# main_board.net
KiCad netlist of a schematic drawn in Altium Designer
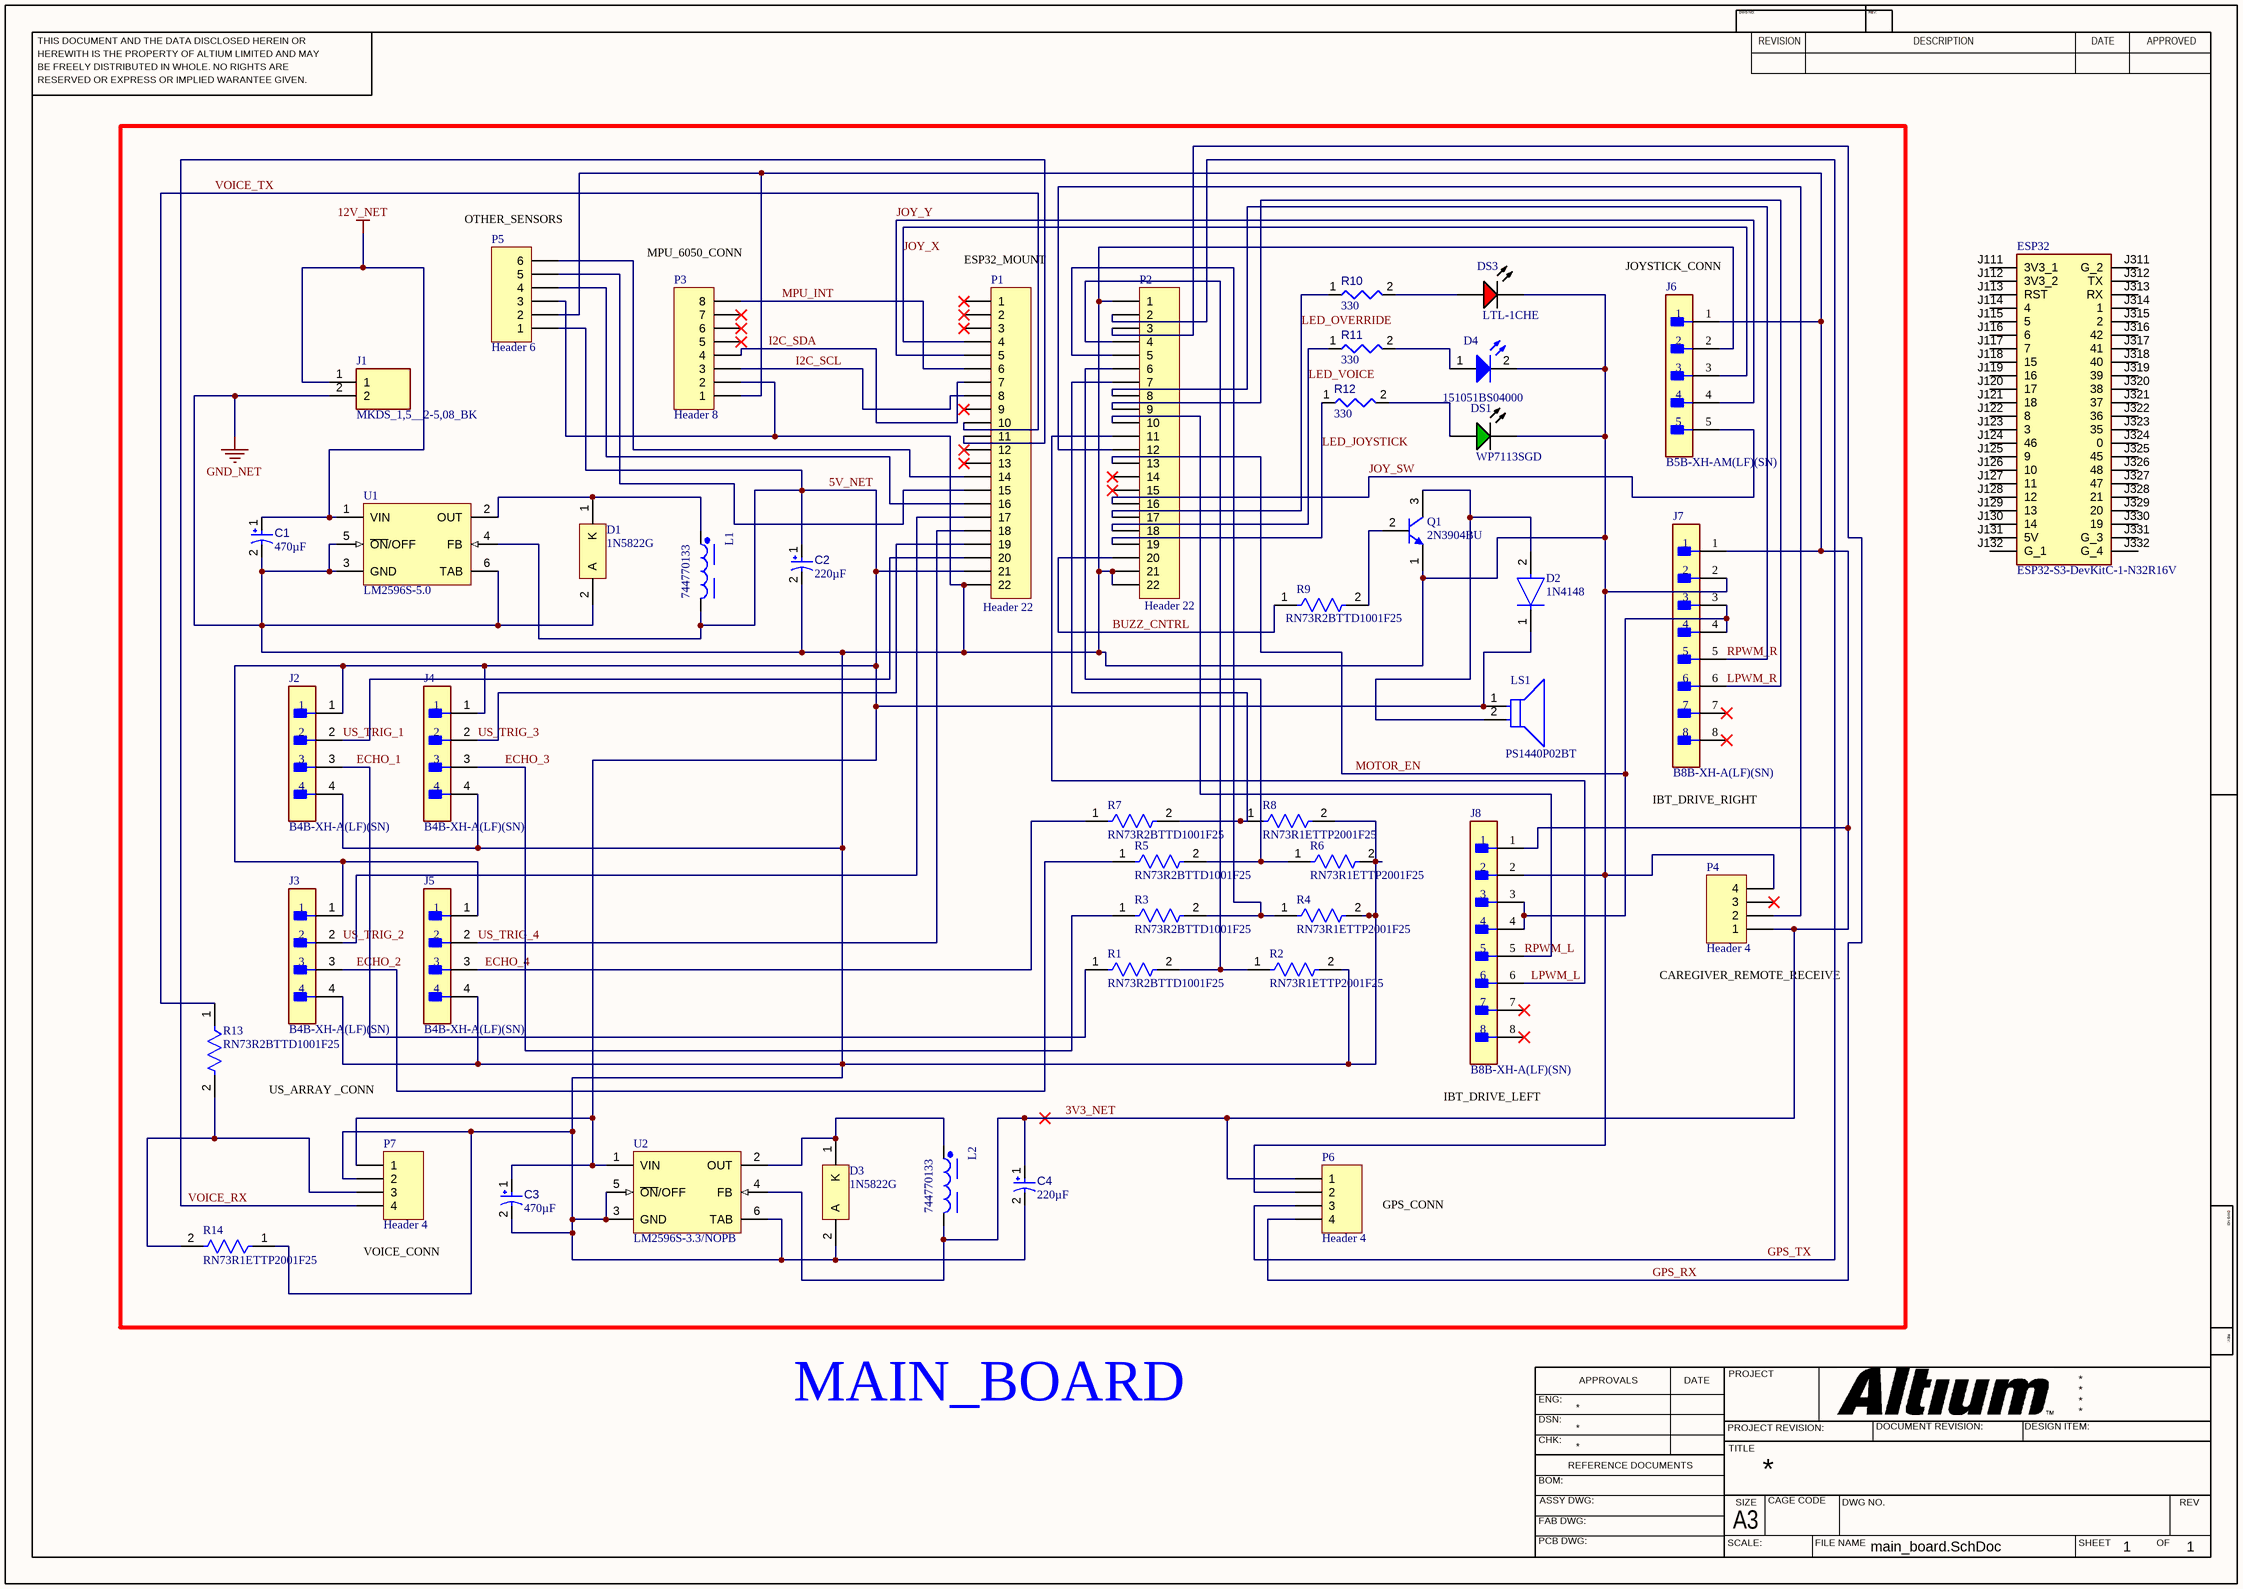
[diagram p0: main_board.SchDoc]

(export (version "E")
  (design (tool "Eeschema 10.0.6"))
  (components
    (comp (ref "C1")
      (value "470µF")
      (footprint "CAPPR65-500-2000X1000X2200")
      (description "Aluminum Electrolytic Capacitor, 470 uF, +/- 20%, 50 V, -40 to 85 degC, 2-Pin THD, RoHS, Bulk")
      (fields (field (name "TOLERANCE") "20%") (field (name "MANUFACTURER") "Panasonic"))
      (libsource (lib "RSM Priyanath") (part "CAP-P-2"))
    )
    (comp (ref "C2")
      (value "220µF")
      (footprint "CAPPR65-500-2000X1000X2200")
      (description "Aluminum Electrolytic Capacitor, 470 uF, +/- 20%, 50 V, -40 to 85 degC, 2-Pin THD, RoHS, Bulk")
      (fields (field (name "TOLERANCE") "20%") (field (name "MANUFACTURER") "Panasonic"))
      (libsource (lib "RSM Priyanath") (part "CAP-P-2"))
    )
    (comp (ref "C3")
      (value "470µF")
      (footprint "CAPPR65-500-2000X1000X2200")
      (description "Aluminum Electrolytic Capacitor, 470 uF, +/- 20%, 50 V, -40 to 85 degC, 2-Pin THD, RoHS, Bulk")
      (fields (field (name "TOLERANCE") "20%") (field (name "MANUFACTURER") "Panasonic"))
      (libsource (lib "RSM Priyanath") (part "CAP-P-2"))
    )
    (comp (ref "C4")
      (value "220µF")
      (footprint "CAPPR65-500-2000X1000X2200")
      (description "Aluminum Electrolytic Capacitor, 470 uF, +/- 20%, 50 V, -40 to 85 degC, 2-Pin THD, RoHS, Bulk")
      (fields (field (name "TOLERANCE") "20%") (field (name "MANUFACTURER") "Panasonic"))
      (libsource (lib "RSM Priyanath") (part "CAP-P-2"))
    )
    (comp (ref "D1")
      (value "1N5822G")
      (footprint "ONSC-AXIAL_LEAD-2-267-05_V")
      (description "Rectifier, 2-Pin Axial_Lead, Pb-Free, Bulk Bag")
      (fields (field (name "MANUFACTURER") "On Semiconductor"))
      (libsource (lib "Altium Content Vault") (part "ONSC-D-K1A2-2_A"))
    )
    (comp (ref "D2")
      (value "1N4148")
      (footprint "FP-017AG-MFG")
      (description "DIODE GEN PURP 100V 200MA DO35")
      (fields (field (name "VOLTAGE") "100V"))
      (libsource (lib "Altium Content Vault") (part "d7152d700b627762746794eb795d46e"))
    )
    (comp (ref "D3")
      (value "1N5822G")
      (footprint "ONSC-AXIAL_LEAD-2-267-05_V")
      (description "Rectifier, 2-Pin Axial_Lead, Pb-Free, Bulk Bag")
      (fields (field (name "MANUFACTURER") "On Semiconductor"))
      (libsource (lib "Altium Content Vault") (part "ONSC-D-K1A2-2_A"))
    )
    (comp (ref "D4")
      (value "151051BS04000")
      (footprint "WL-TMRC_D5.9H8.7")
      (description "Single Color LED, Blue, Diffused, T-1 3/4, 4.9mm")
      (libsource (lib "Altium Content Vault") (part "LED_Blue_1A-2K"))
    )
    (comp (ref "DS1")
      (value "WP7113SGD")
      (footprint "KING-WP7113SGD_V")
      (description "LED Green, 62.5 mW, 25 mA, -40 to 85 degC, 2-Pin THD, RoHS, Bulk")
      (fields (field (name "MANUFACTURER") "Kingbright") (field (name "POWER") "62.5mW"))
      (libsource (lib "RSM Priyanath") (part "LED-GREEN-AK-2"))
    )
    (comp (ref "DS3")
      (value "LTL-1CHE")
      (footprint "INDPR60-254-520X380X650")
      (description "LED Uni-Color Red, 100 mW, 30 mA, -55 to 100 degC, 2-Pin THD, RoHS, Bulk")
      (fields (field (name "MANUFACTURER") "Lite-On"))
      (libsource (lib "RSM Priyanath") (part "LED-RED-AK-2"))
    )
    (comp (ref "ESP32")
      (value "ESP32-S3-DevKitC-1-N32R16V")
      (footprint "SamacSys:ESP32S3DevKitC1N32R16V")
      (description "Undefined or Miscellaneous")
      (fields (field (name "MOUSER PART NUMBER") "356-32S3DKTC1N32R16V"))
      (libsource (lib "*") (part "ESP32-S3-DevKitC-1-N32R16V"))
    )
    (comp (ref "J1")
      (value "MKDS_1,5__2-5,08_BK")
      (footprint "SamacSys:MKDS152508BK")
      (description "Connector")
      (fields (field (name "MANUFACTURER_PART_NUMBER") "MKDS 1,5/ 2-5,08 BK"))
      (libsource (lib "*") (part "MKDS_1,5__2-5,08_BK"))
    )
    (comp (ref "J2")
      (value "B4B-XH-A(LF)(SN)")
      (footprint "FP-B4B-XH-A_LF_SN-MFG")
      (description "CONN HEADER VERT 4POS 2.5MM")
      (libsource (lib "Altium Content Vault") (part "299a8cea1bdcbc3624fe62c390fa72c"))
    )
    (comp (ref "J3")
      (value "B4B-XH-A(LF)(SN)")
      (footprint "FP-B4B-XH-A_LF_SN-MFG")
      (description "CONN HEADER VERT 4POS 2.5MM")
      (libsource (lib "Altium Content Vault") (part "299a8cea1bdcbc3624fe62c390fa72c"))
    )
    (comp (ref "J4")
      (value "B4B-XH-A(LF)(SN)")
      (footprint "FP-B4B-XH-A_LF_SN-MFG")
      (description "CONN HEADER VERT 4POS 2.5MM")
      (libsource (lib "Altium Content Vault") (part "299a8cea1bdcbc3624fe62c390fa72c"))
    )
    (comp (ref "J5")
      (value "B4B-XH-A(LF)(SN)")
      (footprint "FP-B4B-XH-A_LF_SN-MFG")
      (description "CONN HEADER VERT 4POS 2.5MM")
      (libsource (lib "Altium Content Vault") (part "299a8cea1bdcbc3624fe62c390fa72c"))
    )
    (comp (ref "J6")
      (value "B5B-XH-AM(LF)(SN)")
      (footprint "FP-B5B-XH-AM_LF_SN-MFG")
      (description "CONN HEADER VERT 5POS 2.5MM")
      (libsource (lib "Altium Content Vault") (part "bf93c07fd2649a848d0ec8585582aab"))
    )
    (comp (ref "J7")
      (value "B8B-XH-A(LF)(SN)")
      (footprint "FP-B8B-XH-A_LF_SN-MFG")
      (description "CONN HEADER VERT 8POS 2.5MM")
      (libsource (lib "Altium Content Vault") (part "99ec2b232beb5d2356d4d77f6a047f0"))
    )
    (comp (ref "J8")
      (value "B8B-XH-A(LF)(SN)")
      (footprint "FP-B8B-XH-A_LF_SN-MFG")
      (description "CONN HEADER VERT 8POS 2.5MM")
      (libsource (lib "Altium Content Vault") (part "99ec2b232beb5d2356d4d77f6a047f0"))
    )
    (comp (ref "L1")
      (value "744770133")
      (footprint "WE-PD_1280")
      (description "Power Choke Shielded Wirewound 33uH 20% 1KHz Ferrite 3.2A 64mOhm DCR T/R")
      (fields (field (name "TOLERANCE") "20%"))
      (libsource (lib "Altium Content Vault") (part "Inductor - 2"))
    )
    (comp (ref "L2")
      (value "744770133")
      (footprint "WE-PD_1280")
      (description "Power Choke Shielded Wirewound 33uH 20% 1KHz Ferrite 3.2A 64mOhm DCR T/R")
      (fields (field (name "TOLERANCE") "20%"))
      (libsource (lib "Altium Content Vault") (part "Inductor - 2"))
    )
    (comp (ref "LS1")
      (value "PS1440P02BT")
      (footprint "FP-PS1440P02BT-MFG")
      (description "AUDIO PIEZO TRANSDUCER 30V TH")
      (libsource (lib "Altium Content Vault") (part "5f581d31613f872430949aa526fd155"))
    )
    (comp (ref "P1")
      (value "Header 22")
      (footprint "HDR1X22")
      (description "Header, 22-Pin")
      (fields (field (name "PUBLISHER") "Altium Limited"))
      (libsource (lib "RSM Priyanath") (part "Header 22H"))
    )
    (comp (ref "P2")
      (value "Header 22")
      (footprint "HDR1X22")
      (description "Header, 22-Pin")
      (fields (field (name "PUBLISHER") "Altium Limited"))
      (libsource (lib "RSM Priyanath") (part "Header 22H"))
    )
    (comp (ref "P3")
      (value "Header 8")
      (footprint "HDR1X8")
      (description "Header, 8-Pin")
      (fields (field (name "PUBLISHER") "Altium Limited"))
      (libsource (lib "RSM Priyanath") (part "Header 8H"))
    )
    (comp (ref "P4")
      (value "Header 4")
      (footprint "HDR1X4")
      (description "Header, 4-Pin")
      (fields (field (name "PUBLISHER") "Altium Limited"))
      (libsource (lib "") (part "Header 4H_1"))
    )
    (comp (ref "P5")
      (value "Header 6")
      (footprint "HDR1X6")
      (description "Header, 6-Pin")
      (fields (field (name "PUBLISHER") "Altium Limited"))
      (libsource (lib "RSM Priyanath") (part "Header 6H"))
    )
    (comp (ref "P6")
      (value "Header 4")
      (footprint "HDR1X4")
      (description "Header, 4-Pin")
      (fields (field (name "PUBLISHER") "Altium Limited"))
      (libsource (lib "RSM Priyanath") (part "Header 4H"))
    )
    (comp (ref "P7")
      (value "Header 4")
      (footprint "HDR1X4")
      (description "Header, 4-Pin")
      (fields (field (name "PUBLISHER") "Altium Limited"))
      (libsource (lib "RSM Priyanath") (part "Header 4H"))
    )
    (comp (ref "Q1")
      (value "2N3904BU")
      (footprint "FAIR-TO-92")
      (description "NPN General-Purpose Amplifier, 40 V VCEO, 0.2 A, -55 to 150 degC, 2-Pin TO-92, RoHS, Bulk")
      (fields (field (name "MANUFACTURER") "FairchildSemiconductor"))
      (libsource (lib "Altium Content Vault") (part "NPN-E1B2C3-3"))
    )
    (comp (ref "R1")
      (value "RN73R2BTTD1001F25")
      (footprint "FP-RN73R2B-MFG")
      (description "1kΩ ±1% 0.25W, 1/4W Chip Resistor 1206 (3216 Metric) Moisture Resistant Thin Film")
      (libsource (lib "Altium Content Vault") (part "1029c3af85768c4190bb7ad29bc67b5"))
    )
    (comp (ref "R2")
      (value "RN73R1ETTP2001F25")
      (footprint "FP-RN73R1E-IPC_B")
      (description "2kΩ ±1% 0.063W, 1/16W Chip Resistor 0402 (1005 Metric) Moisture Resistant Thin Film")
      (libsource (lib "Altium Content Vault") (part "1029c3af85768c4190bb7ad29bc67b5"))
    )
    (comp (ref "R3")
      (value "RN73R2BTTD1001F25")
      (footprint "FP-RN73R2B-MFG")
      (description "1kΩ ±1% 0.25W, 1/4W Chip Resistor 1206 (3216 Metric) Moisture Resistant Thin Film")
      (libsource (lib "Altium Content Vault") (part "1029c3af85768c4190bb7ad29bc67b5"))
    )
    (comp (ref "R4")
      (value "RN73R1ETTP2001F25")
      (footprint "FP-RN73R1E-IPC_B")
      (description "2kΩ ±1% 0.063W, 1/16W Chip Resistor 0402 (1005 Metric) Moisture Resistant Thin Film")
      (libsource (lib "Altium Content Vault") (part "1029c3af85768c4190bb7ad29bc67b5"))
    )
    (comp (ref "R5")
      (value "RN73R2BTTD1001F25")
      (footprint "FP-RN73R2B-MFG")
      (description "1kΩ ±1% 0.25W, 1/4W Chip Resistor 1206 (3216 Metric) Moisture Resistant Thin Film")
      (libsource (lib "Altium Content Vault") (part "1029c3af85768c4190bb7ad29bc67b5"))
    )
    (comp (ref "R6")
      (value "RN73R1ETTP2001F25")
      (footprint "FP-RN73R1E-IPC_B")
      (description "2kΩ ±1% 0.063W, 1/16W Chip Resistor 0402 (1005 Metric) Moisture Resistant Thin Film")
      (libsource (lib "Altium Content Vault") (part "1029c3af85768c4190bb7ad29bc67b5"))
    )
    (comp (ref "R7")
      (value "RN73R2BTTD1001F25")
      (footprint "FP-RN73R2B-MFG")
      (description "1kΩ ±1% 0.25W, 1/4W Chip Resistor 1206 (3216 Metric) Moisture Resistant Thin Film")
      (libsource (lib "Altium Content Vault") (part "1029c3af85768c4190bb7ad29bc67b5"))
    )
    (comp (ref "R8")
      (value "RN73R1ETTP2001F25")
      (footprint "FP-RN73R1E-IPC_B")
      (description "2kΩ ±1% 0.063W, 1/16W Chip Resistor 0402 (1005 Metric) Moisture Resistant Thin Film")
      (libsource (lib "Altium Content Vault") (part "1029c3af85768c4190bb7ad29bc67b5"))
    )
    (comp (ref "R9")
      (value "RN73R2BTTD1001F25")
      (footprint "FP-RN73R2B-MFG")
      (description "1kΩ ±1% 0.25W, 1/4W Chip Resistor 1206 (3216 Metric) Moisture Resistant Thin Film")
      (libsource (lib "Altium Content Vault") (part "1029c3af85768c4190bb7ad29bc67b5"))
    )
    (comp (ref "R10")
      (value "330")
      (footprint "RESC0402(1005)_L")
      (description "Chip Resistor, 330 Ohms, +/-5 %, 63 mW, -55 to 155 degC, 0402")
      (fields (field (name "POWER") "63mW") (field (name "TOLERANCE") "5%"))
      (libsource (lib "RSM Priyanath") (part "RES-2"))
    )
    (comp (ref "R11")
      (value "330")
      (footprint "RESC0402(1005)_L")
      (description "Chip Resistor, 330 Ohms, +/-5 %, 63 mW, -55 to 155 degC, 0402")
      (fields (field (name "POWER") "63mW") (field (name "TOLERANCE") "5%"))
      (libsource (lib "RSM Priyanath") (part "RES-2"))
    )
    (comp (ref "R12")
      (value "330")
      (footprint "RESC0402(1005)_L")
      (description "Chip Resistor, 330 Ohms, +/-5 %, 63 mW, -55 to 155 degC, 0402")
      (fields (field (name "POWER") "63mW") (field (name "TOLERANCE") "5%"))
      (libsource (lib "RSM Priyanath") (part "RES-2"))
    )
    (comp (ref "R13")
      (value "RN73R2BTTD1001F25")
      (footprint "FP-RN73R2B-MFG")
      (description "1kΩ ±1% 0.25W, 1/4W Chip Resistor 1206 (3216 Metric) Moisture Resistant Thin Film")
      (libsource (lib "Altium Content Vault") (part "1029c3af85768c4190bb7ad29bc67b5"))
    )
    (comp (ref "R14")
      (value "RN73R1ETTP2001F25")
      (footprint "FP-RN73R1E-IPC_B")
      (description "2kΩ ±1% 0.063W, 1/16W Chip Resistor 0402 (1005 Metric) Moisture Resistant Thin Film")
      (libsource (lib "Altium Content Vault") (part "1029c3af85768c4190bb7ad29bc67b5"))
    )
    (comp (ref "U1")
      (value "LM2596S-5.0")
      (footprint "KTT0005B_L")
      (description "SIMPLE SWITCHER® Power Converter 150 KHz 3A Step-Down Voltage Regulator, 5-pin TO-263")
      (fields (field (name "MANUFACTURER") "Texas Instruments"))
      (libsource (lib "Altium Content Vault") (part "PM-REG-LM2575HVS-12"))
    )
    (comp (ref "U2")
      (value "LM2596S-3.3/NOPB")
      (footprint "KTT0005B_M")
      (description "SIMPLE SWITCHER® Power Converter 150 KHz 3A Step-Down Voltage Regulator, 5-pin TO-263, Pb-Free")
      (fields (field (name "MANUFACTURER") "Texas Instruments"))
      (libsource (lib "Altium Content Vault") (part "PM-REG-LM2575HVS-12"))
    )
  )
  (nets
    (net (code "1") (name "/3V3_NET") (class "Default")
      (node (ref "C4") (pin "1") (pinfunction "1_1") (pintype "passive"))
      (node (ref "J6") (pin "1") (pinfunction "1_1") (pintype "passive"))
      (node (ref "J7") (pin "1") (pinfunction "1_1") (pintype "passive"))
      (node (ref "J8") (pin "1") (pinfunction "1_1") (pintype "passive"))
      (node (ref "L2") (pin "2") (pinfunction "2_2") (pintype "passive"))
      (node (ref "P3") (pin "1") (pinfunction "1_1") (pintype "passive"))
      (node (ref "P4") (pin "1") (pinfunction "1_1") (pintype "passive"))
      (node (ref "P5") (pin "2") (pinfunction "2_2") (pintype "passive"))
      (node (ref "P6") (pin "1") (pinfunction "1_1") (pintype "passive"))
      (node (ref "U2") (pin "4") (pinfunction "FB_4") (pintype "input"))
    )
    (net (code "2") (name "/5V_NET") (class "Default")
      (node (ref "C2") (pin "1") (pinfunction "1_1") (pintype "passive"))
      (node (ref "C3") (pin "1") (pinfunction "1_1") (pintype "passive"))
      (node (ref "D2") (pin "1") (pinfunction "C_1") (pintype "passive"))
      (node (ref "J2") (pin "1") (pinfunction "1_1") (pintype "passive"))
      (node (ref "J3") (pin "1") (pinfunction "1_1") (pintype "passive"))
      (node (ref "J4") (pin "1") (pinfunction "1_1") (pintype "passive"))
      (node (ref "J5") (pin "1") (pinfunction "1_1") (pintype "passive"))
      (node (ref "L1") (pin "2") (pinfunction "2_2") (pintype "passive"))
      (node (ref "LS1") (pin "1") (pinfunction "1_1") (pintype "passive"))
      (node (ref "P1") (pin "21") (pinfunction "21_21") (pintype "passive"))
      (node (ref "P5") (pin "1") (pinfunction "1_1") (pintype "passive"))
      (node (ref "P7") (pin "1") (pinfunction "1_1") (pintype "passive"))
      (node (ref "U1") (pin "4") (pinfunction "FB_4") (pintype "input"))
      (node (ref "U2") (pin "1") (pinfunction "VIN_1") (pintype "power_in"))
    )
    (net (code "3") (name "/BUZZ_CNTRL") (class "Default")
      (node (ref "P2") (pin "20") (pinfunction "20_20") (pintype "passive"))
      (node (ref "R9") (pin "1") (pinfunction "1_1") (pintype "passive"))
    )
    (net (code "4") (name "/ECHO_1") (class "Default")
      (node (ref "J2") (pin "3") (pinfunction "3_3") (pintype "passive"))
      (node (ref "R1") (pin "1") (pinfunction "1_1") (pintype "passive"))
    )
    (net (code "5") (name "/ECHO_2") (class "Default")
      (node (ref "J3") (pin "3") (pinfunction "3_3") (pintype "passive"))
      (node (ref "R5") (pin "1") (pinfunction "1_1") (pintype "passive"))
    )
    (net (code "6") (name "/ECHO_3") (class "Default")
      (node (ref "J4") (pin "3") (pinfunction "3_3") (pintype "passive"))
      (node (ref "R3") (pin "1") (pinfunction "1_1") (pintype "passive"))
    )
    (net (code "7") (name "/ECHO_4") (class "Default")
      (node (ref "J5") (pin "3") (pinfunction "3_3") (pintype "passive"))
      (node (ref "R7") (pin "1") (pinfunction "1_1") (pintype "passive"))
    )
    (net (code "8") (name "/GPS_RX") (class "Default")
      (node (ref "P2") (pin "3") (pinfunction "3_3") (pintype "passive"))
      (node (ref "P6") (pin "4") (pinfunction "4_4") (pintype "passive"))
    )
    (net (code "9") (name "/GPS_TX") (class "Default")
      (node (ref "P2") (pin "2") (pinfunction "2_2") (pintype "passive"))
      (node (ref "P6") (pin "3") (pinfunction "3_3") (pintype "passive"))
    )
    (net (code "10") (name "/I2C_SCL") (class "Default")
      (node (ref "P1") (pin "8") (pinfunction "8_8") (pintype "passive"))
      (node (ref "P3") (pin "3") (pinfunction "3_3") (pintype "passive"))
    )
    (net (code "11") (name "/I2C_SDA") (class "Default")
      (node (ref "P1") (pin "7") (pinfunction "7_7") (pintype "passive"))
      (node (ref "P3") (pin "4") (pinfunction "4_4") (pintype "passive"))
    )
    (net (code "12") (name "/JOY_SW") (class "Default")
      (node (ref "J6") (pin "5") (pinfunction "5_5") (pintype "passive"))
      (node (ref "P2") (pin "16") (pinfunction "16_16") (pintype "passive"))
    )
    (net (code "13") (name "/JOY_X") (class "Default")
      (node (ref "J6") (pin "3") (pinfunction "3_3") (pintype "passive"))
      (node (ref "P1") (pin "4") (pinfunction "4_4") (pintype "passive"))
    )
    (net (code "14") (name "/JOY_Y") (class "Default")
      (node (ref "J6") (pin "4") (pinfunction "4_4") (pintype "passive"))
      (node (ref "P1") (pin "5") (pinfunction "5_5") (pintype "passive"))
    )
    (net (code "15") (name "/LED_JOYSTICK") (class "Default")
      (node (ref "P2") (pin "19") (pinfunction "19_19") (pintype "passive"))
      (node (ref "R12") (pin "1") (pinfunction "1_1") (pintype "passive"))
    )
    (net (code "16") (name "/LED_OVERRIDE") (class "Default")
      (node (ref "P2") (pin "17") (pinfunction "17_17") (pintype "passive"))
      (node (ref "R10") (pin "1") (pinfunction "1_1") (pintype "passive"))
    )
    (net (code "17") (name "/LED_VOICE") (class "Default")
      (node (ref "P2") (pin "18") (pinfunction "18_18") (pintype "passive"))
      (node (ref "R11") (pin "1") (pinfunction "1_1") (pintype "passive"))
    )
    (net (code "18") (name "/LPWM_L") (class "Default")
      (node (ref "J8") (pin "6") (pinfunction "6_6") (pintype "passive"))
      (node (ref "P2") (pin "11") (pinfunction "11_11") (pintype "passive"))
    )
    (net (code "19") (name "/LPWM_R") (class "Default")
      (node (ref "J7") (pin "6") (pinfunction "6_6") (pintype "passive"))
      (node (ref "P2") (pin "9") (pinfunction "9_9") (pintype "passive"))
    )
    (net (code "20") (name "/MOTOR_EN") (class "Default")
      (node (ref "J7") (pin "3") (pinfunction "3_3") (pintype "passive"))
      (node (ref "J7") (pin "4") (pinfunction "4_4") (pintype "passive"))
      (node (ref "J8") (pin "3") (pinfunction "3_3") (pintype "passive"))
      (node (ref "J8") (pin "4") (pinfunction "4_4") (pintype "passive"))
      (node (ref "P2") (pin "13") (pinfunction "13_13") (pintype "passive"))
    )
    (net (code "21") (name "/MPU_INT") (class "Default")
      (node (ref "P1") (pin "6") (pinfunction "6_6") (pintype "passive"))
      (node (ref "P3") (pin "8") (pinfunction "8_8") (pintype "passive"))
    )
    (net (code "22") (name "/RPWM_L") (class "Default")
      (node (ref "J8") (pin "5") (pinfunction "5_5") (pintype "passive"))
      (node (ref "P2") (pin "10") (pinfunction "10_10") (pintype "passive"))
    )
    (net (code "23") (name "/RPWM_R") (class "Default")
      (node (ref "J7") (pin "5") (pinfunction "5_5") (pintype "passive"))
      (node (ref "P2") (pin "8") (pinfunction "8_8") (pintype "passive"))
    )
    (net (code "24") (name "/US_TRIG_1") (class "Default")
      (node (ref "J2") (pin "2") (pinfunction "2_2") (pintype "passive"))
      (node (ref "P1") (pin "20") (pinfunction "20_20") (pintype "passive"))
    )
    (net (code "25") (name "/US_TRIG_2") (class "Default")
      (node (ref "J3") (pin "2") (pinfunction "2_2") (pintype "passive"))
      (node (ref "P1") (pin "17") (pinfunction "17_17") (pintype "passive"))
    )
    (net (code "26") (name "/US_TRIG_3") (class "Default")
      (node (ref "J4") (pin "2") (pinfunction "2_2") (pintype "passive"))
      (node (ref "P1") (pin "19") (pinfunction "19_19") (pintype "passive"))
    )
    (net (code "27") (name "/US_TRIG_4") (class "Default")
      (node (ref "J5") (pin "2") (pinfunction "2_2") (pintype "passive"))
      (node (ref "P1") (pin "18") (pinfunction "18_18") (pintype "passive"))
    )
    (net (code "28") (name "/VOICE_RX") (class "Default")
      (node (ref "P1") (pin "11") (pinfunction "11_11") (pintype "passive"))
      (node (ref "P7") (pin "4") (pinfunction "4_4") (pintype "passive"))
    )
    (net (code "29") (name "/VOICE_TX") (class "Default")
      (node (ref "P1") (pin "10") (pinfunction "10_10") (pintype "passive"))
      (node (ref "R13") (pin "1") (pinfunction "1_1") (pintype "passive"))
    )
    (net (code "30") (name "12V_NET") (class "Default")
      (node (ref "C1") (pin "1") (pinfunction "1_1") (pintype "passive"))
      (node (ref "J1") (pin "1") (pinfunction "1_1") (pintype "passive"))
      (node (ref "U1") (pin "1") (pinfunction "VIN_1") (pintype "power_in"))
    )
    (net (code "31") (name "GND_NET") (class "Default")
      (node (ref "C1") (pin "2") (pinfunction "2_2") (pintype "passive"))
      (node (ref "C2") (pin "2") (pinfunction "2_2") (pintype "passive"))
      (node (ref "C3") (pin "2") (pinfunction "2_2") (pintype "passive"))
      (node (ref "C4") (pin "2") (pinfunction "2_2") (pintype "passive"))
      (node (ref "D1") (pin "2") (pinfunction "A_2") (pintype "passive"))
      (node (ref "D3") (pin "2") (pinfunction "A_2") (pintype "passive"))
      (node (ref "D4") (pin "2") (pinfunction "K_2") (pintype "passive"))
      (node (ref "DS1") (pin "2") (pinfunction "K_2") (pintype "passive"))
      (node (ref "DS3") (pin "2") (pinfunction "K_2") (pintype "passive"))
      (node (ref "J1") (pin "2") (pinfunction "2_2") (pintype "passive"))
      (node (ref "J2") (pin "4") (pinfunction "4_4") (pintype "passive"))
      (node (ref "J3") (pin "4") (pinfunction "4_4") (pintype "passive"))
      (node (ref "J4") (pin "4") (pinfunction "4_4") (pintype "passive"))
      (node (ref "J5") (pin "4") (pinfunction "4_4") (pintype "passive"))
      (node (ref "J6") (pin "2") (pinfunction "2_2") (pintype "passive"))
      (node (ref "J7") (pin "2") (pinfunction "2_2") (pintype "passive"))
      (node (ref "J8") (pin "2") (pinfunction "2_2") (pintype "passive"))
      (node (ref "P1") (pin "22") (pinfunction "22_22") (pintype "passive"))
      (node (ref "P2") (pin "1") (pinfunction "1_1") (pintype "passive"))
      (node (ref "P2") (pin "21") (pinfunction "21_21") (pintype "passive"))
      (node (ref "P2") (pin "22") (pinfunction "22_22") (pintype "passive"))
      (node (ref "P3") (pin "2") (pinfunction "2_2") (pintype "passive"))
      (node (ref "P4") (pin "4") (pinfunction "4_4") (pintype "passive"))
      (node (ref "P5") (pin "3") (pinfunction "3_3") (pintype "passive"))
      (node (ref "P6") (pin "2") (pinfunction "2_2") (pintype "passive"))
      (node (ref "P7") (pin "2") (pinfunction "2_2") (pintype "passive"))
      (node (ref "Q1") (pin "1") (pinfunction "E_1") (pintype "passive"))
      (node (ref "R14") (pin "1") (pinfunction "1_1") (pintype "passive"))
      (node (ref "R2") (pin "2") (pinfunction "2_2") (pintype "passive"))
      (node (ref "R4") (pin "2") (pinfunction "2_2") (pintype "passive"))
      (node (ref "R6") (pin "2") (pinfunction "2_2") (pintype "passive"))
      (node (ref "R8") (pin "2") (pinfunction "2_2") (pintype "passive"))
      (node (ref "U1") (pin "3") (pinfunction "GND_3") (pintype "power_in"))
      (node (ref "U1") (pin "5") (pinfunction "~{ON}/OFF_5") (pintype "input"))
      (node (ref "U1") (pin "6") (pinfunction "TAB_6") (pintype "power_in"))
      (node (ref "U2") (pin "3") (pinfunction "GND_3") (pintype "power_in"))
      (node (ref "U2") (pin "5") (pinfunction "~{ON}/OFF_5") (pintype "input"))
      (node (ref "U2") (pin "6") (pinfunction "TAB_6") (pintype "power_in"))
    )
    (net (code "32") (name "Net-(D1-K)") (class "Default")
      (node (ref "D1") (pin "1") (pinfunction "K_1") (pintype "passive"))
      (node (ref "L1") (pin "1") (pinfunction "1_1") (pintype "passive"))
      (node (ref "U1") (pin "2") (pinfunction "OUT_2") (pintype "power_in"))
    )
    (net (code "33") (name "Net-(D2-A)") (class "Default")
      (node (ref "D2") (pin "2") (pinfunction "A_2") (pintype "passive"))
      (node (ref "LS1") (pin "2") (pinfunction "2_2") (pintype "passive"))
      (node (ref "Q1") (pin "3") (pinfunction "C_3") (pintype "passive"))
    )
    (net (code "34") (name "Net-(D3-K)") (class "Default")
      (node (ref "D3") (pin "1") (pinfunction "K_1") (pintype "passive"))
      (node (ref "L2") (pin "1") (pinfunction "1_1") (pintype "passive"))
      (node (ref "U2") (pin "2") (pinfunction "OUT_2") (pintype "power_in"))
    )
    (net (code "35") (name "Net-(D4-A)") (class "Default")
      (node (ref "D4") (pin "1") (pinfunction "A_1") (pintype "passive"))
      (node (ref "R11") (pin "2") (pinfunction "2_2") (pintype "passive"))
    )
    (net (code "36") (name "Net-(DS1-A)") (class "Default")
      (node (ref "DS1") (pin "1") (pinfunction "A_1") (pintype "passive"))
      (node (ref "R12") (pin "2") (pinfunction "2_2") (pintype "passive"))
    )
    (net (code "37") (name "Net-(DS3-A)") (class "Default")
      (node (ref "DS3") (pin "1") (pinfunction "A_1") (pintype "passive"))
      (node (ref "R10") (pin "2") (pinfunction "2_2") (pintype "passive"))
    )
    (net (code "38") (name "Net-(P1-Pad14)") (class "Default")
      (node (ref "P1") (pin "14") (pinfunction "14_14") (pintype "passive"))
      (node (ref "P5") (pin "6") (pinfunction "6_6") (pintype "passive"))
    )
    (net (code "39") (name "Net-(P1-Pad15)") (class "Default")
      (node (ref "P1") (pin "15") (pinfunction "15_15") (pintype "passive"))
      (node (ref "P5") (pin "5") (pinfunction "5_5") (pintype "passive"))
    )
    (net (code "40") (name "Net-(P1-Pad16)") (class "Default")
      (node (ref "P1") (pin "16") (pinfunction "16_16") (pintype "passive"))
      (node (ref "P5") (pin "4") (pinfunction "4_4") (pintype "passive"))
    )
    (net (code "41") (name "Net-(P2-Pad4)") (class "Default")
      (node (ref "P2") (pin "4") (pinfunction "4_4") (pintype "passive"))
      (node (ref "R1") (pin "2") (pinfunction "2_2") (pintype "passive"))
      (node (ref "R2") (pin "1") (pinfunction "1_1") (pintype "passive"))
    )
    (net (code "42") (name "Net-(P2-Pad5)") (class "Default")
      (node (ref "P2") (pin "5") (pinfunction "5_5") (pintype "passive"))
      (node (ref "R3") (pin "2") (pinfunction "2_2") (pintype "passive"))
      (node (ref "R4") (pin "1") (pinfunction "1_1") (pintype "passive"))
    )
    (net (code "43") (name "Net-(P2-Pad6)") (class "Default")
      (node (ref "P2") (pin "6") (pinfunction "6_6") (pintype "passive"))
      (node (ref "R5") (pin "2") (pinfunction "2_2") (pintype "passive"))
      (node (ref "R6") (pin "1") (pinfunction "1_1") (pintype "passive"))
    )
    (net (code "44") (name "Net-(P2-Pad7)") (class "Default")
      (node (ref "P2") (pin "7") (pinfunction "7_7") (pintype "passive"))
      (node (ref "R7") (pin "2") (pinfunction "2_2") (pintype "passive"))
      (node (ref "R8") (pin "1") (pinfunction "1_1") (pintype "passive"))
    )
    (net (code "45") (name "Net-(P2-Pad12)") (class "Default")
      (node (ref "P2") (pin "12") (pinfunction "12_12") (pintype "passive"))
      (node (ref "P4") (pin "2") (pinfunction "2_2") (pintype "passive"))
    )
    (net (code "46") (name "Net-(P7-Pad3)") (class "Default")
      (node (ref "P7") (pin "3") (pinfunction "3_3") (pintype "passive"))
      (node (ref "R13") (pin "2") (pinfunction "2_2") (pintype "passive"))
      (node (ref "R14") (pin "2") (pinfunction "2_2") (pintype "passive"))
    )
    (net (code "47") (name "Net-(Q1-B)") (class "Default")
      (node (ref "Q1") (pin "2") (pinfunction "B_2") (pintype "passive"))
      (node (ref "R9") (pin "2") (pinfunction "2_2") (pintype "passive"))
    )
    (net (code "48") (name "unconnected-(ESP32-0-PadJ324)") (class "Default")
      (node (ref "ESP32") (pin "J324") (pinfunction "0_J324") (pintype "passive"))
    )
    (net (code "49") (name "unconnected-(ESP32-1-PadJ314)") (class "Default")
      (node (ref "ESP32") (pin "J314") (pinfunction "1_J314") (pintype "passive"))
    )
    (net (code "50") (name "unconnected-(ESP32-2-PadJ315)") (class "Default")
      (node (ref "ESP32") (pin "J315") (pinfunction "2_J315") (pintype "passive"))
    )
    (net (code "51") (name "unconnected-(ESP32-3-PadJ123)") (class "Default")
      (node (ref "ESP32") (pin "J123") (pinfunction "3_J123") (pintype "passive"))
    )
    (net (code "52") (name "unconnected-(ESP32-3V3_1-PadJ111)") (class "Default")
      (node (ref "ESP32") (pin "J111") (pinfunction "3V3_1_J111") (pintype "passive"))
    )
    (net (code "53") (name "unconnected-(ESP32-3V3_2-PadJ112)") (class "Default")
      (node (ref "ESP32") (pin "J112") (pinfunction "3V3_2_J112") (pintype "passive"))
    )
    (net (code "54") (name "unconnected-(ESP32-4-PadJ114)") (class "Default")
      (node (ref "ESP32") (pin "J114") (pinfunction "4_J114") (pintype "passive"))
    )
    (net (code "55") (name "unconnected-(ESP32-5-PadJ115)") (class "Default")
      (node (ref "ESP32") (pin "J115") (pinfunction "5_J115") (pintype "passive"))
    )
    (net (code "56") (name "unconnected-(ESP32-5V-PadJ131)") (class "Default")
      (node (ref "ESP32") (pin "J131") (pinfunction "5V_J131") (pintype "passive"))
    )
    (net (code "57") (name "unconnected-(ESP32-6-PadJ116)") (class "Default")
      (node (ref "ESP32") (pin "J116") (pinfunction "6_J116") (pintype "passive"))
    )
    (net (code "58") (name "unconnected-(ESP32-7-PadJ117)") (class "Default")
      (node (ref "ESP32") (pin "J117") (pinfunction "7_J117") (pintype "passive"))
    )
    (net (code "59") (name "unconnected-(ESP32-8-PadJ122)") (class "Default")
      (node (ref "ESP32") (pin "J122") (pinfunction "8_J122") (pintype "passive"))
    )
    (net (code "60") (name "unconnected-(ESP32-9-PadJ125)") (class "Default")
      (node (ref "ESP32") (pin "J125") (pinfunction "9_J125") (pintype "passive"))
    )
    (net (code "61") (name "unconnected-(ESP32-10-PadJ126)") (class "Default")
      (node (ref "ESP32") (pin "J126") (pinfunction "10_J126") (pintype "passive"))
    )
    (net (code "62") (name "unconnected-(ESP32-11-PadJ127)") (class "Default")
      (node (ref "ESP32") (pin "J127") (pinfunction "11_J127") (pintype "passive"))
    )
    (net (code "63") (name "unconnected-(ESP32-12-PadJ128)") (class "Default")
      (node (ref "ESP32") (pin "J128") (pinfunction "12_J128") (pintype "passive"))
    )
    (net (code "64") (name "unconnected-(ESP32-13-PadJ129)") (class "Default")
      (node (ref "ESP32") (pin "J129") (pinfunction "13_J129") (pintype "passive"))
    )
    (net (code "65") (name "unconnected-(ESP32-14-PadJ130)") (class "Default")
      (node (ref "ESP32") (pin "J130") (pinfunction "14_J130") (pintype "passive"))
    )
    (net (code "66") (name "unconnected-(ESP32-15-PadJ118)") (class "Default")
      (node (ref "ESP32") (pin "J118") (pinfunction "15_J118") (pintype "passive"))
    )
    (net (code "67") (name "unconnected-(ESP32-16-PadJ119)") (class "Default")
      (node (ref "ESP32") (pin "J119") (pinfunction "16_J119") (pintype "passive"))
    )
    (net (code "68") (name "unconnected-(ESP32-17-PadJ120)") (class "Default")
      (node (ref "ESP32") (pin "J120") (pinfunction "17_J120") (pintype "passive"))
    )
    (net (code "69") (name "unconnected-(ESP32-18-PadJ121)") (class "Default")
      (node (ref "ESP32") (pin "J121") (pinfunction "18_J121") (pintype "passive"))
    )
    (net (code "70") (name "unconnected-(ESP32-19-PadJ330)") (class "Default")
      (node (ref "ESP32") (pin "J330") (pinfunction "19_J330") (pintype "passive"))
    )
    (net (code "71") (name "unconnected-(ESP32-20-PadJ329)") (class "Default")
      (node (ref "ESP32") (pin "J329") (pinfunction "20_J329") (pintype "passive"))
    )
    (net (code "72") (name "unconnected-(ESP32-21-PadJ328)") (class "Default")
      (node (ref "ESP32") (pin "J328") (pinfunction "21_J328") (pintype "passive"))
    )
    (net (code "73") (name "unconnected-(ESP32-35-PadJ323)") (class "Default")
      (node (ref "ESP32") (pin "J323") (pinfunction "35_J323") (pintype "passive"))
    )
    (net (code "74") (name "unconnected-(ESP32-36-PadJ322)") (class "Default")
      (node (ref "ESP32") (pin "J322") (pinfunction "36_J322") (pintype "passive"))
    )
    (net (code "75") (name "unconnected-(ESP32-37-PadJ321)") (class "Default")
      (node (ref "ESP32") (pin "J321") (pinfunction "37_J321") (pintype "passive"))
    )
    (net (code "76") (name "unconnected-(ESP32-38-PadJ320)") (class "Default")
      (node (ref "ESP32") (pin "J320") (pinfunction "38_J320") (pintype "passive"))
    )
    (net (code "77") (name "unconnected-(ESP32-39-PadJ319)") (class "Default")
      (node (ref "ESP32") (pin "J319") (pinfunction "39_J319") (pintype "passive"))
    )
    (net (code "78") (name "unconnected-(ESP32-40-PadJ318)") (class "Default")
      (node (ref "ESP32") (pin "J318") (pinfunction "40_J318") (pintype "passive"))
    )
    (net (code "79") (name "unconnected-(ESP32-41-PadJ317)") (class "Default")
      (node (ref "ESP32") (pin "J317") (pinfunction "41_J317") (pintype "passive"))
    )
    (net (code "80") (name "unconnected-(ESP32-42-PadJ316)") (class "Default")
      (node (ref "ESP32") (pin "J316") (pinfunction "42_J316") (pintype "passive"))
    )
    (net (code "81") (name "unconnected-(ESP32-45-PadJ325)") (class "Default")
      (node (ref "ESP32") (pin "J325") (pinfunction "45_J325") (pintype "passive"))
    )
    (net (code "82") (name "unconnected-(ESP32-46-PadJ124)") (class "Default")
      (node (ref "ESP32") (pin "J124") (pinfunction "46_J124") (pintype "passive"))
    )
    (net (code "83") (name "unconnected-(ESP32-47-PadJ327)") (class "Default")
      (node (ref "ESP32") (pin "J327") (pinfunction "47_J327") (pintype "passive"))
    )
    (net (code "84") (name "unconnected-(ESP32-48-PadJ326)") (class "Default")
      (node (ref "ESP32") (pin "J326") (pinfunction "48_J326") (pintype "passive"))
    )
    (net (code "85") (name "unconnected-(ESP32-G_1-PadJ132)") (class "Default")
      (node (ref "ESP32") (pin "J132") (pinfunction "G_1_J132") (pintype "passive"))
    )
    (net (code "86") (name "unconnected-(ESP32-G_2-PadJ311)") (class "Default")
      (node (ref "ESP32") (pin "J311") (pinfunction "G_2_J311") (pintype "passive"))
    )
    (net (code "87") (name "unconnected-(ESP32-G_3-PadJ331)") (class "Default")
      (node (ref "ESP32") (pin "J331") (pinfunction "G_3_J331") (pintype "passive"))
    )
    (net (code "88") (name "unconnected-(ESP32-G_4-PadJ332)") (class "Default")
      (node (ref "ESP32") (pin "J332") (pinfunction "G_4_J332") (pintype "passive"))
    )
    (net (code "89") (name "unconnected-(ESP32-RST-PadJ113)") (class "Default")
      (node (ref "ESP32") (pin "J113") (pinfunction "RST_J113") (pintype "passive"))
    )
    (net (code "90") (name "unconnected-(ESP32-RX-PadJ313)") (class "Default")
      (node (ref "ESP32") (pin "J313") (pinfunction "RX_J313") (pintype "passive"))
    )
    (net (code "91") (name "unconnected-(ESP32-TX-PadJ312)") (class "Default")
      (node (ref "ESP32") (pin "J312") (pinfunction "TX_J312") (pintype "passive"))
    )
    (net (code "92") (name "unconnected-(J7-Pad7)") (class "Default")
      (node (ref "J7") (pin "7") (pinfunction "7_7") (pintype "passive+no_connect"))
    )
    (net (code "93") (name "unconnected-(J7-Pad8)") (class "Default")
      (node (ref "J7") (pin "8") (pinfunction "8_8") (pintype "passive+no_connect"))
    )
    (net (code "94") (name "unconnected-(J8-Pad7)") (class "Default")
      (node (ref "J8") (pin "7") (pinfunction "7_7") (pintype "passive+no_connect"))
    )
    (net (code "95") (name "unconnected-(J8-Pad8)") (class "Default")
      (node (ref "J8") (pin "8") (pinfunction "8_8") (pintype "passive+no_connect"))
    )
    (net (code "96") (name "unconnected-(P1-Pad1)") (class "Default")
      (node (ref "P1") (pin "1") (pinfunction "1_1") (pintype "passive+no_connect"))
    )
    (net (code "97") (name "unconnected-(P1-Pad2)") (class "Default")
      (node (ref "P1") (pin "2") (pinfunction "2_2") (pintype "passive+no_connect"))
    )
    (net (code "98") (name "unconnected-(P1-Pad3)") (class "Default")
      (node (ref "P1") (pin "3") (pinfunction "3_3") (pintype "passive+no_connect"))
    )
    (net (code "99") (name "unconnected-(P1-Pad9)") (class "Default")
      (node (ref "P1") (pin "9") (pinfunction "9_9") (pintype "passive+no_connect"))
    )
    (net (code "100") (name "unconnected-(P1-Pad12)") (class "Default")
      (node (ref "P1") (pin "12") (pinfunction "12_12") (pintype "passive+no_connect"))
    )
    (net (code "101") (name "unconnected-(P1-Pad13)") (class "Default")
      (node (ref "P1") (pin "13") (pinfunction "13_13") (pintype "passive+no_connect"))
    )
    (net (code "102") (name "unconnected-(P2-Pad14)") (class "Default")
      (node (ref "P2") (pin "14") (pinfunction "14_14") (pintype "passive+no_connect"))
    )
    (net (code "103") (name "unconnected-(P2-Pad15)") (class "Default")
      (node (ref "P2") (pin "15") (pinfunction "15_15") (pintype "passive+no_connect"))
    )
    (net (code "104") (name "unconnected-(P3-Pad5)") (class "Default")
      (node (ref "P3") (pin "5") (pinfunction "5_5") (pintype "passive+no_connect"))
    )
    (net (code "105") (name "unconnected-(P3-Pad6)") (class "Default")
      (node (ref "P3") (pin "6") (pinfunction "6_6") (pintype "passive+no_connect"))
    )
    (net (code "106") (name "unconnected-(P3-Pad7)") (class "Default")
      (node (ref "P3") (pin "7") (pinfunction "7_7") (pintype "passive+no_connect"))
    )
    (net (code "107") (name "unconnected-(P4-Pad3)") (class "Default")
      (node (ref "P4") (pin "3") (pinfunction "3_3") (pintype "passive+no_connect"))
    )
  )
)
